# sch_sensor.net
KiCad netlist of a schematic drawn in Altium Designer
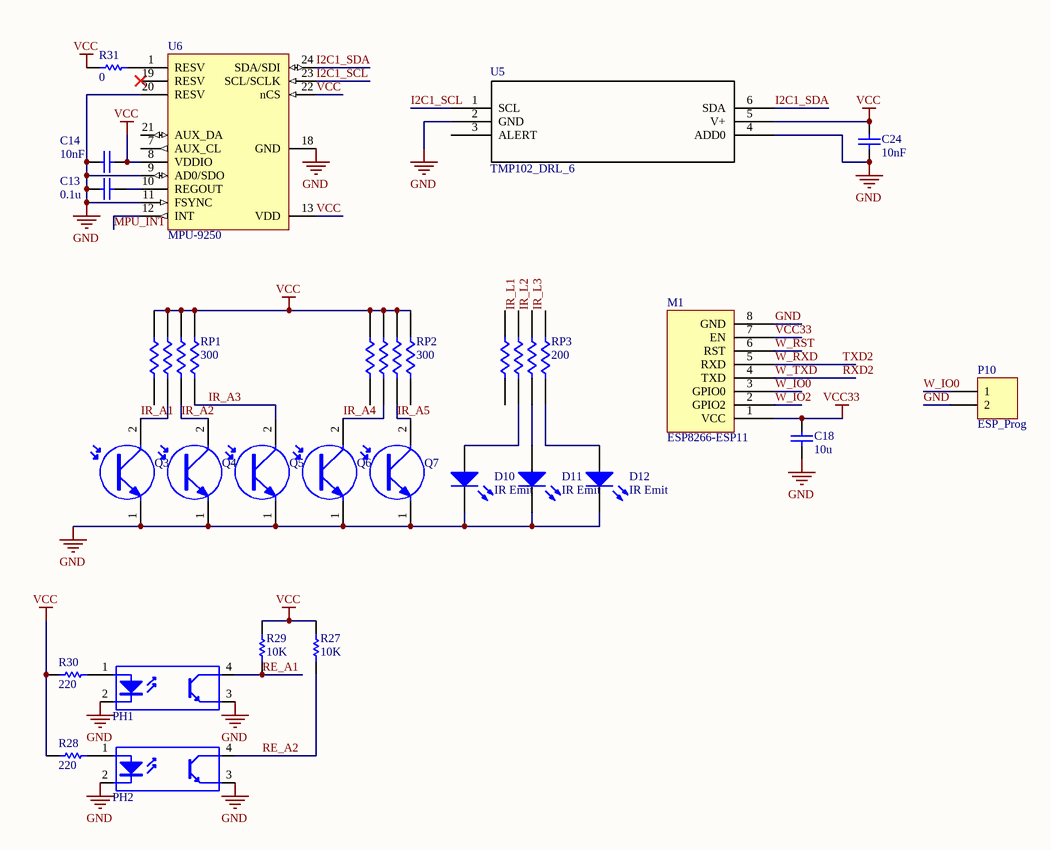
[diagram p0: sch_sensor.SchDoc]

(export (version "E")
  (design (tool "Eeschema 10.0.6"))
  (components
    (comp (ref "C13")
      (value "0.1u")
      (footprint "C-1608[0603]")
      (description "Capacitor (Semiconductor SIM Model)")
      (fields (field (name "Comment") "Cap Semi") (field (name "PUBLISHER") "Altium Limited"))
      (libsource (lib "Miscellaneous Devices") (part "Cap Semi"))
    )
    (comp (ref "C14")
      (value "10nF")
      (footprint "C-1608[0603]")
      (description "Capacitor (Semiconductor SIM Model)")
      (fields (field (name "Comment") "Cap Semi") (field (name "PUBLISHER") "Altium Limited"))
      (libsource (lib "Miscellaneous Devices") (part "Cap Semi"))
    )
    (comp (ref "C18")
      (value "10u")
      (footprint "C-1608[0603]")
      (description "Capacitor (Semiconductor SIM Model)")
      (fields (field (name "Comment") "Cap Semi") (field (name "PUBLISHER") "Altium Limited"))
      (libsource (lib "Miscellaneous Devices") (part "Cap Semi"))
    )
    (comp (ref "C24")
      (value "10nF")
      (footprint "C-1608[0603]")
      (description "Capacitor (Semiconductor SIM Model)")
      (fields (field (name "Comment") "Cap Semi") (field (name "PUBLISHER") "Altium Limited"))
      (libsource (lib "Miscellaneous Devices") (part "Cap Semi"))
    )
    (comp (ref "D10")
      (value "IR Emit")
      (footprint "LED-0")
      (description "Typical INFRARED GaAs LED")
      (fields (field (name "PUBLISHER") "Altium Limited"))
      (libsource (lib "Miscellaneous Devices") (part "LED0"))
    )
    (comp (ref "D11")
      (value "IR Emit")
      (footprint "LED-0")
      (description "Typical INFRARED GaAs LED")
      (fields (field (name "PUBLISHER") "Altium Limited"))
      (libsource (lib "Miscellaneous Devices") (part "LED0"))
    )
    (comp (ref "D12")
      (value "IR Emit")
      (footprint "LED-0")
      (description "Typical INFRARED GaAs LED")
      (fields (field (name "PUBLISHER") "Altium Limited"))
      (libsource (lib "Miscellaneous Devices") (part "LED0"))
    )
    (comp (ref "M1")
      (value "ESP8266-ESP11")
      (footprint "ESP8266-ESP11")
      (libsource (lib "WiFiMod") (part "ESP8266-ESP11"))
    )
    (comp (ref "P10")
      (value "ESP_Prog")
      (footprint "EDGE_1")
      (description "Header, 2-Pin")
      (fields (field (name "PUBLISHER") "Altium Limited"))
      (libsource (lib "Miscellaneous Connectors") (part "Header 2"))
    )
    (comp (ref "PH1")
      (value "Optoisolator1")
      (footprint "RPR359F")
      (description "4-Pin Phototransistor Optocoupler")
      (fields (field (name "PUBLISHER") "Altium Limited"))
      (libsource (lib "Miscellaneous Devices") (part "Optoisolator1"))
    )
    (comp (ref "PH2")
      (value "Optoisolator1")
      (footprint "RPR359F")
      (description "4-Pin Phototransistor Optocoupler")
      (fields (field (name "PUBLISHER") "Altium Limited"))
      (libsource (lib "Miscellaneous Devices") (part "Optoisolator1"))
    )
    (comp (ref "Q3")
      (value "IR_Photo_NPN")
      (footprint "PHOTO_NPN")
      (description "NPN Phototransistor")
      (fields (field (name "PUBLISHER") "Altium Limited"))
      (libsource (lib "general") (part "IR_Photo_NPN"))
    )
    (comp (ref "Q4")
      (value "IR_Photo_NPN")
      (footprint "PHOTO_NPN")
      (description "NPN Phototransistor")
      (fields (field (name "PUBLISHER") "Altium Limited"))
      (libsource (lib "general") (part "IR_Photo_NPN"))
    )
    (comp (ref "Q5")
      (value "IR_Photo_NPN")
      (footprint "PHOTO_NPN")
      (description "NPN Phototransistor")
      (fields (field (name "PUBLISHER") "Altium Limited"))
      (libsource (lib "general") (part "IR_Photo_NPN"))
    )
    (comp (ref "Q6")
      (value "IR_Photo_NPN")
      (footprint "PHOTO_NPN")
      (description "NPN Phototransistor")
      (fields (field (name "PUBLISHER") "Altium Limited"))
      (libsource (lib "general") (part "IR_Photo_NPN"))
    )
    (comp (ref "Q7")
      (value "IR_Photo_NPN")
      (footprint "PHOTO_NPN")
      (description "NPN Phototransistor")
      (fields (field (name "PUBLISHER") "Altium Limited"))
      (libsource (lib "general") (part "IR_Photo_NPN"))
    )
    (comp (ref "R27")
      (value "10K")
      (footprint "R-1608[0603]")
      (description "Semiconductor Resistor")
      (fields (field (name "Comment") "Res Semi") (field (name "PUBLISHER") "Altium Limited"))
      (libsource (lib "Miscellaneous Devices") (part "Res Semi"))
    )
    (comp (ref "R28")
      (value "220")
      (footprint "R-1608[0603]")
      (description "Semiconductor Resistor")
      (fields (field (name "Comment") "Res Semi") (field (name "PUBLISHER") "Altium Limited"))
      (libsource (lib "Miscellaneous Devices") (part "Res Semi"))
    )
    (comp (ref "R29")
      (value "10K")
      (footprint "R-1608[0603]")
      (description "Semiconductor Resistor")
      (fields (field (name "Comment") "Res Semi") (field (name "PUBLISHER") "Altium Limited"))
      (libsource (lib "Miscellaneous Devices") (part "Res Semi"))
    )
    (comp (ref "R30")
      (value "220")
      (footprint "R-1608[0603]")
      (description "Semiconductor Resistor")
      (fields (field (name "Comment") "Res Semi") (field (name "PUBLISHER") "Altium Limited"))
      (libsource (lib "Miscellaneous Devices") (part "Res Semi"))
    )
    (comp (ref "R31")
      (value "0")
      (footprint "R-1608[0603]")
      (description "Semiconductor Resistor")
      (fields (field (name "Comment") "Res Semi") (field (name "PUBLISHER") "Altium Limited"))
      (libsource (lib "Miscellaneous Devices") (part "Res Semi"))
    )
    (comp (ref "RP1") (value "300") (footprint "R0603x4") (libsource (lib "general") (part "RPACK4")))
    (comp (ref "RP2") (value "300") (footprint "R0603x4") (libsource (lib "general") (part "RPACK4")))
    (comp (ref "RP3") (value "200") (footprint "R0603x4") (libsource (lib "general") (part "RPACK4")))
    (comp (ref "U5")
      (value "TMP102_DRL_6")
      (footprint "DRL6")
      (description "Imported")
      (fields
        (field (name "MANUFACTURER_PART_NUMBER") "tmp102_drl_6")
        (field (name "GENERIC_PART_NUMBER") "TMP102")
      )
      (libsource (lib "TMP102") (part "TMP102_DRL_6"))
    )
    (comp (ref "U6")
      (value "MPU-9250")
      (footprint "MPU9250")
      (description "Integrated 6-axis MotionTracking device")
      (libsource (lib "general") (part "MPU-9250"))
    )
  )
  (nets
    (net (code "1") (name "/I2C1_SCL") (class "Default")
      (node (ref "U5") (pin "1") (pinfunction "SCL_1") (pintype "passive"))
      (node (ref "U6") (pin "23") (pinfunction "SCL/SCLK_23") (pintype "input"))
    )
    (net (code "2") (name "/I2C1_SDA") (class "Default")
      (node (ref "U5") (pin "6") (pinfunction "SDA_6") (pintype "passive"))
      (node (ref "U6") (pin "24") (pinfunction "SDA/SDI_24") (pintype "bidirectional"))
    )
    (net (code "3") (name "/IR_A1") (class "Default")
      (node (ref "Q3") (pin "2") (pinfunction "C_2") (pintype "passive"))
      (node (ref "RP1") (pin "6") (pinfunction "6_6") (pintype "passive"))
    )
    (net (code "4") (name "/IR_A2") (class "Default")
      (node (ref "Q4") (pin "2") (pinfunction "C_2") (pintype "passive"))
      (node (ref "RP1") (pin "7") (pinfunction "7_7") (pintype "passive"))
    )
    (net (code "5") (name "/IR_A3") (class "Default")
      (node (ref "Q5") (pin "2") (pinfunction "C_2") (pintype "passive"))
      (node (ref "RP1") (pin "8") (pinfunction "8_8") (pintype "passive"))
    )
    (net (code "6") (name "/IR_A4") (class "Default")
      (node (ref "Q6") (pin "2") (pinfunction "C_2") (pintype "passive"))
      (node (ref "RP2") (pin "6") (pinfunction "6_6") (pintype "passive"))
    )
    (net (code "7") (name "/IR_A5") (class "Default")
      (node (ref "Q7") (pin "2") (pinfunction "C_2") (pintype "passive"))
      (node (ref "RP2") (pin "7") (pinfunction "7_7") (pintype "passive"))
    )
    (net (code "8") (name "/IR_L1") (class "Default")
      (node (ref "RP3") (pin "3") (pinfunction "3_3") (pintype "passive"))
    )
    (net (code "9") (name "/IR_L2") (class "Default")
      (node (ref "RP3") (pin "2") (pinfunction "2_2") (pintype "passive"))
    )
    (net (code "10") (name "/IR_L3") (class "Default")
      (node (ref "RP3") (pin "1") (pinfunction "1_1") (pintype "passive"))
    )
    (net (code "11") (name "/MPU_INT") (class "Default")
      (node (ref "U6") (pin "12") (pinfunction "INT_12") (pintype "output"))
    )
    (net (code "12") (name "/RE_A1") (class "Default")
      (node (ref "PH1") (pin "4") (pinfunction "C_4") (pintype "passive"))
      (node (ref "R29") (pin "1") (pinfunction "1_1") (pintype "passive"))
    )
    (net (code "13") (name "/RE_A2") (class "Default")
      (node (ref "PH2") (pin "4") (pinfunction "C_4") (pintype "passive"))
      (node (ref "R27") (pin "1") (pinfunction "1_1") (pintype "passive"))
    )
    (net (code "14") (name "/RXD2") (class "Default")
      (node (ref "M1") (pin "4") (pinfunction "TXD_4") (pintype "passive"))
    )
    (net (code "15") (name "/TXD2") (class "Default")
      (node (ref "M1") (pin "5") (pinfunction "RXD_5") (pintype "passive"))
    )
    (net (code "16") (name "/W_IO0") (class "Default")
      (node (ref "M1") (pin "3") (pinfunction "GPIO0_3") (pintype "passive"))
      (node (ref "P10") (pin "1") (pinfunction "1_1") (pintype "passive"))
    )
    (net (code "17") (name "/W_IO2") (class "Default")
      (node (ref "M1") (pin "2") (pinfunction "GPIO2_2") (pintype "passive"))
    )
    (net (code "18") (name "/W_RST") (class "Default")
      (node (ref "M1") (pin "6") (pinfunction "RST_6") (pintype "passive"))
    )
    (net (code "19") (name "GND") (class "Default")
      (node (ref "C13") (pin "2") (pinfunction "2_2") (pintype "passive"))
      (node (ref "C14") (pin "2") (pinfunction "2_2") (pintype "passive"))
      (node (ref "C18") (pin "1") (pinfunction "1_1") (pintype "passive"))
      (node (ref "C24") (pin "2") (pinfunction "2_2") (pintype "passive"))
      (node (ref "D10") (pin "2") (pinfunction "K_2") (pintype "passive"))
      (node (ref "D11") (pin "2") (pinfunction "K_2") (pintype "passive"))
      (node (ref "D12") (pin "2") (pinfunction "K_2") (pintype "passive"))
      (node (ref "M1") (pin "8") (pinfunction "GND_8") (pintype "passive"))
      (node (ref "P10") (pin "2") (pinfunction "2_2") (pintype "passive"))
      (node (ref "PH1") (pin "2") (pinfunction "K_2") (pintype "passive"))
      (node (ref "PH1") (pin "3") (pinfunction "E_3") (pintype "passive"))
      (node (ref "PH2") (pin "2") (pinfunction "K_2") (pintype "passive"))
      (node (ref "PH2") (pin "3") (pinfunction "E_3") (pintype "passive"))
      (node (ref "Q3") (pin "1") (pinfunction "E_1") (pintype "passive"))
      (node (ref "Q4") (pin "1") (pinfunction "E_1") (pintype "passive"))
      (node (ref "Q5") (pin "1") (pinfunction "E_1") (pintype "passive"))
      (node (ref "Q6") (pin "1") (pinfunction "E_1") (pintype "passive"))
      (node (ref "Q7") (pin "1") (pinfunction "E_1") (pintype "passive"))
      (node (ref "U5") (pin "2") (pinfunction "GND_2") (pintype "power_in"))
      (node (ref "U5") (pin "4") (pinfunction "ADD0_4") (pintype "passive"))
      (node (ref "U6") (pin "11") (pinfunction "FSYNC_11") (pintype "input"))
      (node (ref "U6") (pin "18") (pinfunction "GND_18") (pintype "power_in"))
      (node (ref "U6") (pin "20") (pinfunction "RESV_20") (pintype "passive"))
      (node (ref "U6") (pin "9") (pinfunction "AD0/SDO_9") (pintype "bidirectional"))
    )
    (net (code "20") (name "Net-(D10-A)") (class "Default")
      (node (ref "D10") (pin "1") (pinfunction "A_1") (pintype "passive"))
      (node (ref "RP3") (pin "6") (pinfunction "6_6") (pintype "passive"))
    )
    (net (code "21") (name "Net-(D11-A)") (class "Default")
      (node (ref "D11") (pin "1") (pinfunction "A_1") (pintype "passive"))
      (node (ref "RP3") (pin "7") (pinfunction "7_7") (pintype "passive"))
    )
    (net (code "22") (name "Net-(D12-A)") (class "Default")
      (node (ref "D12") (pin "1") (pinfunction "A_1") (pintype "passive"))
      (node (ref "RP3") (pin "8") (pinfunction "8_8") (pintype "passive"))
    )
    (net (code "23") (name "Net-(PH1-A)") (class "Default")
      (node (ref "PH1") (pin "1") (pinfunction "A_1") (pintype "passive"))
      (node (ref "R30") (pin "1") (pinfunction "1_1") (pintype "passive"))
    )
    (net (code "24") (name "Net-(PH2-A)") (class "Default")
      (node (ref "PH2") (pin "1") (pinfunction "A_1") (pintype "passive"))
      (node (ref "R28") (pin "1") (pinfunction "1_1") (pintype "passive"))
    )
    (net (code "25") (name "Net-(R31-Pad2)") (class "Default")
      (node (ref "R31") (pin "2") (pinfunction "2_2") (pintype "passive"))
      (node (ref "U6") (pin "1") (pinfunction "RESV_1") (pintype "passive"))
    )
    (net (code "26") (name "Net-(U6-REGOUT)") (class "Default")
      (node (ref "C13") (pin "1") (pinfunction "1_1") (pintype "passive"))
      (node (ref "U6") (pin "10") (pinfunction "REGOUT_10") (pintype "passive"))
    )
    (net (code "27") (name "VCC") (class "Default")
      (node (ref "C14") (pin "1") (pinfunction "1_1") (pintype "passive"))
      (node (ref "C24") (pin "1") (pinfunction "1_1") (pintype "passive"))
      (node (ref "R27") (pin "2") (pinfunction "2_2") (pintype "passive"))
      (node (ref "R28") (pin "2") (pinfunction "2_2") (pintype "passive"))
      (node (ref "R29") (pin "2") (pinfunction "2_2") (pintype "passive"))
      (node (ref "R30") (pin "2") (pinfunction "2_2") (pintype "passive"))
      (node (ref "R31") (pin "1") (pinfunction "1_1") (pintype "passive"))
      (node (ref "RP1") (pin "1") (pinfunction "1_1") (pintype "passive"))
      (node (ref "RP1") (pin "2") (pinfunction "2_2") (pintype "passive"))
      (node (ref "RP1") (pin "3") (pinfunction "3_3") (pintype "passive"))
      (node (ref "RP1") (pin "4") (pinfunction "4_4") (pintype "passive"))
      (node (ref "RP2") (pin "1") (pinfunction "1_1") (pintype "passive"))
      (node (ref "RP2") (pin "2") (pinfunction "2_2") (pintype "passive"))
      (node (ref "RP2") (pin "3") (pinfunction "3_3") (pintype "passive"))
      (node (ref "RP2") (pin "4") (pinfunction "4_4") (pintype "passive"))
      (node (ref "U5") (pin "5") (pinfunction "V+_5") (pintype "power_in"))
      (node (ref "U6") (pin "13") (pinfunction "VDD_13") (pintype "power_in"))
      (node (ref "U6") (pin "22") (pinfunction "nCS_22") (pintype "input"))
      (node (ref "U6") (pin "8") (pinfunction "VDDIO_8") (pintype "power_in"))
    )
    (net (code "28") (name "VCC33") (class "Default")
      (node (ref "C18") (pin "2") (pinfunction "2_2") (pintype "passive"))
      (node (ref "M1") (pin "1") (pinfunction "VCC_1") (pintype "power_in"))
      (node (ref "M1") (pin "7") (pinfunction "EN_7") (pintype "passive"))
    )
    (net (code "29") (name "unconnected-(RP1-Pad5)") (class "Default")
      (node (ref "RP1") (pin "5") (pinfunction "5_5") (pintype "passive"))
    )
    (net (code "30") (name "unconnected-(RP2-Pad5)") (class "Default")
      (node (ref "RP2") (pin "5") (pinfunction "5_5") (pintype "passive"))
    )
    (net (code "31") (name "unconnected-(RP2-Pad8)") (class "Default")
      (node (ref "RP2") (pin "8") (pinfunction "8_8") (pintype "passive"))
    )
    (net (code "32") (name "unconnected-(RP3-Pad4)") (class "Default")
      (node (ref "RP3") (pin "4") (pinfunction "4_4") (pintype "passive"))
    )
    (net (code "33") (name "unconnected-(RP3-Pad5)") (class "Default")
      (node (ref "RP3") (pin "5") (pinfunction "5_5") (pintype "passive"))
    )
    (net (code "34") (name "unconnected-(U5-ALERT-Pad3)") (class "Default")
      (node (ref "U5") (pin "3") (pinfunction "ALERT_3") (pintype "passive"))
    )
    (net (code "35") (name "unconnected-(U6-AUX_CL-Pad7)") (class "Default")
      (node (ref "U6") (pin "7") (pinfunction "AUX_CL_7") (pintype "output"))
    )
    (net (code "36") (name "unconnected-(U6-AUX_DA-Pad21)") (class "Default")
      (node (ref "U6") (pin "21") (pinfunction "AUX_DA_21") (pintype "bidirectional"))
    )
    (net (code "37") (name "unconnected-(U6-RESV-Pad19)") (class "Default")
      (node (ref "U6") (pin "19") (pinfunction "RESV_19") (pintype "passive+no_connect"))
    )
  )
)
